# Sheet1.net
KiCad netlist of a schematic drawn in Altium Designer
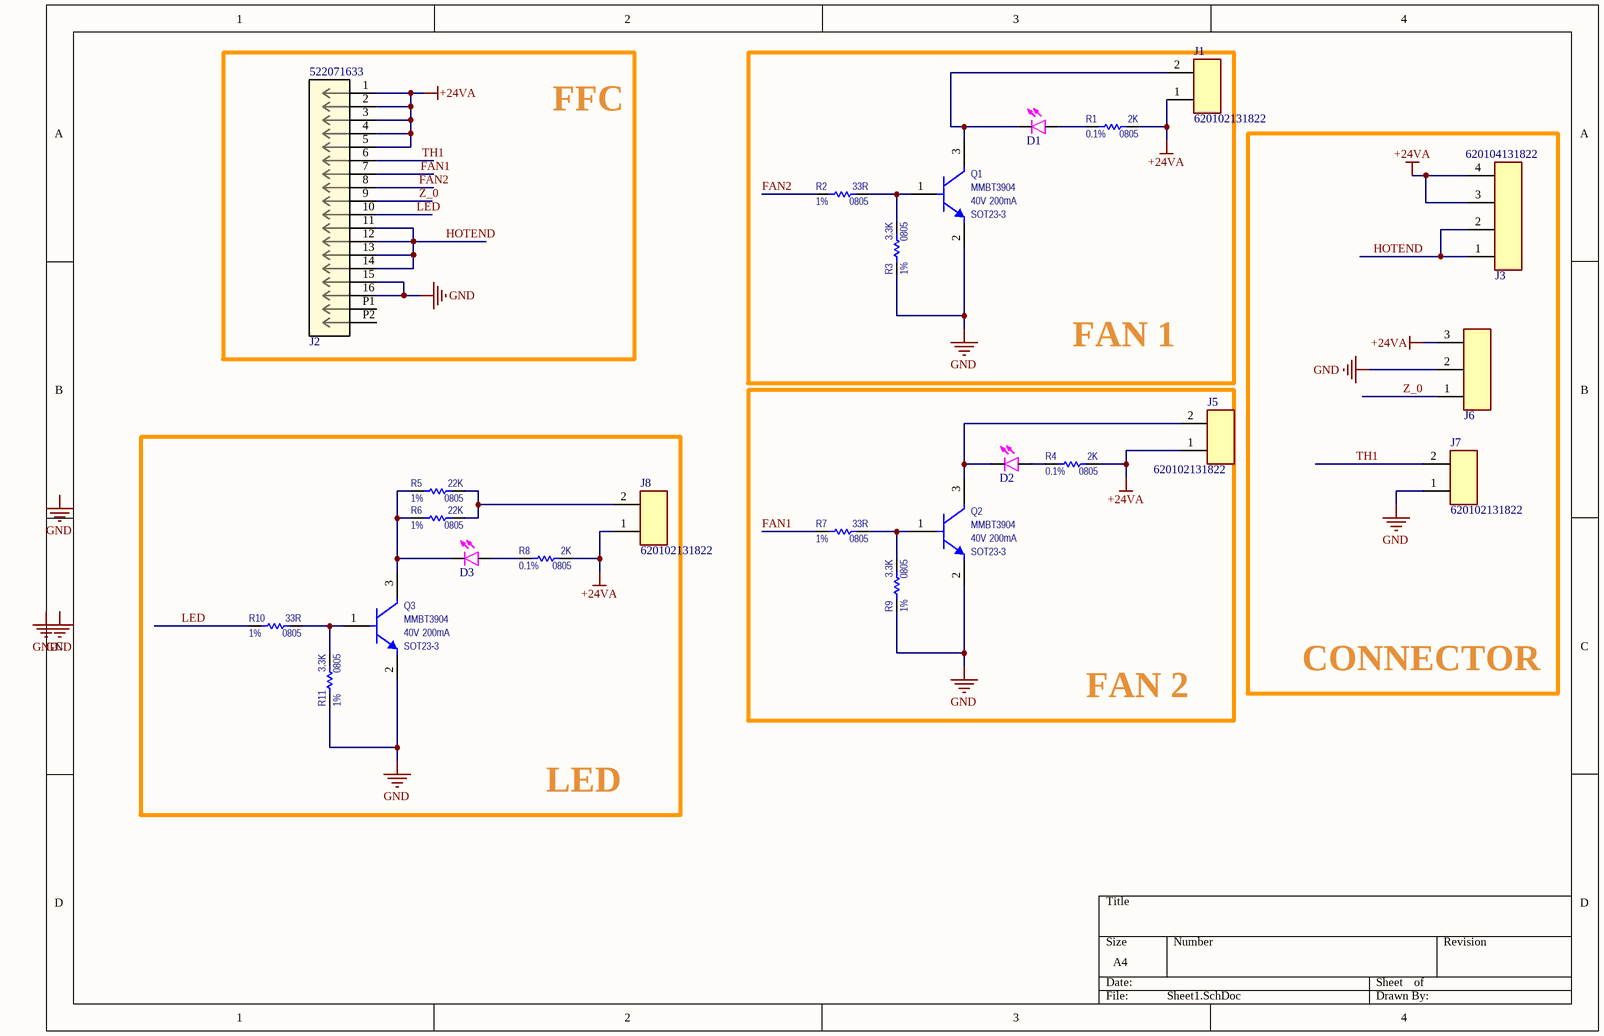
[diagram p0: Sheet1.SchDoc]

(export (version "E")
  (design (tool "Eeschema 10.0.6"))
  (components
    (comp (ref "D1")
      (value "KP-2012SRC-PRV")
      (footprint "0805 LED")
      (description "KP-2012SRC-PRV Red LED, 640 nm 2012 (0805), Rectangle Lens SMD package")
      (fields (field (name "MANUFACTURER") "Kingbright"))
      (libsource (lib "Schlib1") (part "KP-2012SRC-PRV"))
    )
    (comp (ref "D2")
      (value "KP-2012SRC-PRV")
      (footprint "0805 LED")
      (description "KP-2012SRC-PRV Red LED, 640 nm 2012 (0805), Rectangle Lens SMD package")
      (fields (field (name "MANUFACTURER") "Kingbright"))
      (libsource (lib "Schlib1") (part "KP-2012SRC-PRV"))
    )
    (comp (ref "D3")
      (value "KP-2012SRC-PRV")
      (footprint "0805 LED")
      (description "KP-2012SRC-PRV Red LED, 640 nm 2012 (0805), Rectangle Lens SMD package")
      (fields (field (name "MANUFACTURER") "Kingbright"))
      (libsource (lib "Schlib1") (part "KP-2012SRC-PRV"))
    )
    (comp (ref "J1")
      (value "620102131822")
      (footprint "620102131822")
      (description "Connector Header Surface Mount, Right Angle 2 position 0.079 _2.00mm_")
      (fields (field (name "MF") "Wurth Electronics"))
      (libsource (lib "Schlib1") (part "620102131822"))
    )
    (comp (ref "J2")
      (value "522071633")
      (footprint "CON_522071633_MOL")
      (description "No Description Available")
      (libsource (lib "Schlib1") (part "522071633"))
    )
    (comp (ref "J3")
      (value "620104131822")
      (footprint "620104131822")
      (libsource (lib "Schlib1") (part "620104131822"))
    )
    (comp (ref "J5")
      (value "620102131822")
      (footprint "620102131822")
      (description "Connector Header Surface Mount, Right Angle 2 position 0.079 _2.00mm_")
      (fields (field (name "MF") "Wurth Electronics"))
      (libsource (lib "Schlib1") (part "620102131822"))
    )
    (comp (ref "J6")
      (value "620103131822")
      (footprint "620103131822")
      (description "Connector Header Surface Mount, Right Angle 3 position 0.079 (2.00mm)")
      (fields (field (name "MF") "Wurth Electronics"))
      (libsource (lib "Schlib1") (part "620103131822"))
    )
    (comp (ref "J7")
      (value "620102131822")
      (footprint "620102131822")
      (description "Connector Header Surface Mount, Right Angle 2 position 0.079 _2.00mm_")
      (fields (field (name "MF") "Wurth Electronics"))
      (libsource (lib "Schlib1") (part "620102131822"))
    )
    (comp (ref "J8")
      (value "620102131822")
      (footprint "620102131822")
      (description "Connector Header Surface Mount, Right Angle 2 position 0.079 _2.00mm_")
      (fields (field (name "MF") "Wurth Electronics"))
      (libsource (lib "Schlib1") (part "620102131822"))
    )
    (comp (ref "Q1")
      (value "MMBT3904")
      (footprint "SOT23-3_MMBT3904,215")
      (description "TRA_NPN_SING_40V_200mA_VSAT300mV_SOT23-3")
      (fields
        (field (name "CURRENT") "200mA")
        (field (name "VOLTAGE") "40V")
        (field (name "PACKAGE") "SOT23-3")
        (field (name "SIMILAR PART") "SST3904HZGT116; PMBT3904,235")
        (field (name "TOLERANCE") "X")
        (field (name "ADDED BY") "HasanA")
        (field (name "CHECKED BY") "EserC")
      )
      (libsource (lib "FireANTs_HwLibDB") (part "SingleNPN_B1E2C3"))
    )
    (comp (ref "Q2")
      (value "MMBT3904")
      (footprint "SOT23-3_MMBT3904,215")
      (description "TRA_NPN_SING_40V_200mA_VSAT300mV_SOT23-3")
      (fields
        (field (name "CURRENT") "200mA")
        (field (name "VOLTAGE") "40V")
        (field (name "PACKAGE") "SOT23-3")
        (field (name "SIMILAR PART") "SST3904HZGT116; PMBT3904,235")
        (field (name "TOLERANCE") "X")
        (field (name "ADDED BY") "HasanA")
        (field (name "CHECKED BY") "EserC")
      )
      (libsource (lib "FireANTs_HwLibDB") (part "SingleNPN_B1E2C3"))
    )
    (comp (ref "Q3")
      (value "MMBT3904")
      (footprint "SOT23-3_MMBT3904,215")
      (description "TRA_NPN_SING_40V_200mA_VSAT300mV_SOT23-3")
      (fields
        (field (name "CURRENT") "200mA")
        (field (name "VOLTAGE") "40V")
        (field (name "PACKAGE") "SOT23-3")
        (field (name "SIMILAR PART") "SST3904HZGT116; PMBT3904,235")
        (field (name "TOLERANCE") "X")
        (field (name "ADDED BY") "HasanA")
        (field (name "CHECKED BY") "EserC")
      )
      (libsource (lib "FireANTs_HwLibDB") (part "SingleNPN_B1E2C3"))
    )
    (comp (ref "R1")
      (value "2K")
      (footprint "R_0805_GEN_0.70H")
      (description "RES_STD_2K_0.125W_0.1%_25ppm_0805")
      (fields
        (field (name "TOLERANCE") "0.1%")
        (field (name "PACKAGE") "0805")
        (field (name "SIMILAR PART") "ERA-6ARB202V")
        (field (name "VOLTAGE") "100V")
        (field (name "ADDED BY") "İlhanT")
        (field (name "CHECKED BY") "YasinY")
      )
      (libsource (lib "FireANTs_HwLibDB") (part "StandardResistor"))
    )
    (comp (ref "R2")
      (value "33R")
      (footprint "R_0805_GEN_0.70H")
      (description "RES_STD_33R_0.125W_1%_100ppm_0805")
      (fields
        (field (name "TOLERANCE") "1%")
        (field (name "PACKAGE") "0805")
        (field (name "VOLTAGE") "150V")
        (field (name "Comment") "StandardResistor")
        (field (name "ADDED BY") "HasanA")
        (field (name "CHECKED BY") "YasinY")
      )
      (libsource (lib "FireANTs_HwLibDB") (part "StandardResistor"))
    )
    (comp (ref "R3")
      (value "3.3K")
      (footprint "R_0805_GEN_0.70H")
      (description "RES_STD_3.3K_0.125W_1%_100ppm_0805")
      (fields
        (field (name "TOLERANCE") "1%")
        (field (name "PACKAGE") "0805")
        (field (name "VOLTAGE") "150V")
        (field (name "Comment") "StandardResistor")
        (field (name "ADDED BY") "HasanA")
        (field (name "CHECKED BY") "YasinY")
      )
      (libsource (lib "FireANTs_HwLibDB") (part "StandardResistor"))
    )
    (comp (ref "R4")
      (value "2K")
      (footprint "R_0805_GEN_0.70H")
      (description "RES_STD_2K_0.125W_0.1%_25ppm_0805")
      (fields
        (field (name "TOLERANCE") "0.1%")
        (field (name "PACKAGE") "0805")
        (field (name "SIMILAR PART") "ERA-6ARB202V")
        (field (name "VOLTAGE") "100V")
        (field (name "ADDED BY") "İlhanT")
        (field (name "CHECKED BY") "YasinY")
      )
      (libsource (lib "FireANTs_HwLibDB") (part "StandardResistor"))
    )
    (comp (ref "R5")
      (value "22K")
      (footprint "R_0805_GEN_0.70H")
      (description "RES_STD_33R_0.125W_1%_100ppm_0805")
      (fields
        (field (name "TOLERANCE") "1%")
        (field (name "PACKAGE") "0805")
        (field (name "VOLTAGE") "150V")
        (field (name "Comment") "StandardResistor")
        (field (name "ADDED BY") "HasanA")
        (field (name "CHECKED BY") "YasinY")
      )
      (libsource (lib "FireANTs_HwLibDB") (part "StandardResistor"))
    )
    (comp (ref "R6")
      (value "22K")
      (footprint "R_0805_GEN_0.70H")
      (description "RES_STD_33R_0.125W_1%_100ppm_0805")
      (fields
        (field (name "TOLERANCE") "1%")
        (field (name "PACKAGE") "0805")
        (field (name "VOLTAGE") "150V")
        (field (name "Comment") "StandardResistor")
        (field (name "ADDED BY") "HasanA")
        (field (name "CHECKED BY") "YasinY")
      )
      (libsource (lib "FireANTs_HwLibDB") (part "StandardResistor"))
    )
    (comp (ref "R7")
      (value "33R")
      (footprint "R_0805_GEN_0.70H")
      (description "RES_STD_33R_0.125W_1%_100ppm_0805")
      (fields
        (field (name "TOLERANCE") "1%")
        (field (name "PACKAGE") "0805")
        (field (name "VOLTAGE") "150V")
        (field (name "Comment") "StandardResistor")
        (field (name "ADDED BY") "HasanA")
        (field (name "CHECKED BY") "YasinY")
      )
      (libsource (lib "FireANTs_HwLibDB") (part "StandardResistor"))
    )
    (comp (ref "R8")
      (value "2K")
      (footprint "R_0805_GEN_0.70H")
      (description "RES_STD_2K_0.125W_0.1%_25ppm_0805")
      (fields
        (field (name "TOLERANCE") "0.1%")
        (field (name "PACKAGE") "0805")
        (field (name "SIMILAR PART") "ERA-6ARB202V")
        (field (name "VOLTAGE") "100V")
        (field (name "ADDED BY") "İlhanT")
        (field (name "CHECKED BY") "YasinY")
      )
      (libsource (lib "FireANTs_HwLibDB") (part "StandardResistor"))
    )
    (comp (ref "R9")
      (value "3.3K")
      (footprint "R_0805_GEN_0.70H")
      (description "RES_STD_3.3K_0.125W_1%_100ppm_0805")
      (fields
        (field (name "TOLERANCE") "1%")
        (field (name "PACKAGE") "0805")
        (field (name "VOLTAGE") "150V")
        (field (name "Comment") "StandardResistor")
        (field (name "ADDED BY") "HasanA")
        (field (name "CHECKED BY") "YasinY")
      )
      (libsource (lib "FireANTs_HwLibDB") (part "StandardResistor"))
    )
    (comp (ref "R10")
      (value "33R")
      (footprint "R_0805_GEN_0.70H")
      (description "RES_STD_33R_0.125W_1%_100ppm_0805")
      (fields
        (field (name "TOLERANCE") "1%")
        (field (name "PACKAGE") "0805")
        (field (name "VOLTAGE") "150V")
        (field (name "Comment") "StandardResistor")
        (field (name "ADDED BY") "HasanA")
        (field (name "CHECKED BY") "YasinY")
      )
      (libsource (lib "FireANTs_HwLibDB") (part "StandardResistor"))
    )
    (comp (ref "R11")
      (value "3.3K")
      (footprint "R_0805_GEN_0.70H")
      (description "RES_STD_3.3K_0.125W_1%_100ppm_0805")
      (fields
        (field (name "TOLERANCE") "1%")
        (field (name "PACKAGE") "0805")
        (field (name "VOLTAGE") "150V")
        (field (name "Comment") "StandardResistor")
        (field (name "ADDED BY") "HasanA")
        (field (name "CHECKED BY") "YasinY")
      )
      (libsource (lib "FireANTs_HwLibDB") (part "StandardResistor"))
    )
  )
  (nets
    (net (code "1") (name "+24VA") (class "Default")
      (node (ref "J1") (pin "1") (pinfunction "2_1") (pintype "passive"))
      (node (ref "J2") (pin "1") (pinfunction "1_1") (pintype "passive"))
      (node (ref "J2") (pin "2") (pinfunction "2_2") (pintype "passive"))
      (node (ref "J2") (pin "3") (pinfunction "3_3") (pintype "passive"))
      (node (ref "J2") (pin "4") (pinfunction "4_4") (pintype "passive"))
      (node (ref "J2") (pin "5") (pinfunction "5_5") (pintype "passive"))
      (node (ref "J3") (pin "3") (pinfunction "2_3") (pintype "passive"))
      (node (ref "J3") (pin "4") (pinfunction "1_4") (pintype "passive"))
      (node (ref "J5") (pin "1") (pinfunction "2_1") (pintype "passive"))
      (node (ref "J6") (pin "3") (pinfunction "1_3") (pintype "passive"))
      (node (ref "J8") (pin "1") (pinfunction "2_1") (pintype "passive"))
      (node (ref "R1") (pin "2") (pinfunction "2_2") (pintype "passive"))
      (node (ref "R4") (pin "2") (pinfunction "2_2") (pintype "passive"))
      (node (ref "R8") (pin "2") (pinfunction "2_2") (pintype "passive"))
    )
    (net (code "2") (name "/FAN1") (class "Default")
      (node (ref "J2") (pin "7") (pinfunction "7_7") (pintype "passive"))
      (node (ref "R7") (pin "1") (pinfunction "1_1") (pintype "passive"))
    )
    (net (code "3") (name "/FAN2") (class "Default")
      (node (ref "J2") (pin "8") (pinfunction "8_8") (pintype "passive"))
      (node (ref "R2") (pin "1") (pinfunction "1_1") (pintype "passive"))
    )
    (net (code "4") (name "/HOTEND") (class "Default")
      (node (ref "J2") (pin "11") (pinfunction "11_11") (pintype "passive"))
      (node (ref "J2") (pin "12") (pinfunction "12_12") (pintype "passive"))
      (node (ref "J2") (pin "13") (pinfunction "13_13") (pintype "passive"))
      (node (ref "J2") (pin "14") (pinfunction "14_14") (pintype "passive"))
      (node (ref "J3") (pin "1") (pinfunction "4_1") (pintype "passive"))
      (node (ref "J3") (pin "2") (pinfunction "3_2") (pintype "passive"))
    )
    (net (code "5") (name "/LED") (class "Default")
      (node (ref "J2") (pin "10") (pinfunction "10_10") (pintype "passive"))
      (node (ref "R10") (pin "1") (pinfunction "1_1") (pintype "passive"))
    )
    (net (code "6") (name "/TH1") (class "Default")
      (node (ref "J2") (pin "6") (pinfunction "6_6") (pintype "passive"))
      (node (ref "J7") (pin "2") (pinfunction "1_2") (pintype "passive"))
    )
    (net (code "7") (name "/Z_0") (class "Default")
      (node (ref "J2") (pin "9") (pinfunction "9_9") (pintype "passive"))
      (node (ref "J6") (pin "1") (pinfunction "3_1") (pintype "passive"))
    )
    (net (code "8") (name "GND") (class "Default")
      (node (ref "J2") (pin "15") (pinfunction "15_15") (pintype "passive"))
      (node (ref "J2") (pin "16") (pinfunction "16_16") (pintype "passive"))
      (node (ref "J6") (pin "2") (pinfunction "2_2") (pintype "passive"))
      (node (ref "J7") (pin "1") (pinfunction "2_1") (pintype "passive"))
      (node (ref "Q1") (pin "2") (pinfunction "EMITTER_2") (pintype "passive"))
      (node (ref "Q2") (pin "2") (pinfunction "EMITTER_2") (pintype "passive"))
      (node (ref "Q3") (pin "2") (pinfunction "EMITTER_2") (pintype "passive"))
      (node (ref "R11") (pin "1") (pinfunction "1_1") (pintype "passive"))
      (node (ref "R3") (pin "1") (pinfunction "1_1") (pintype "passive"))
      (node (ref "R9") (pin "1") (pinfunction "1_1") (pintype "passive"))
    )
    (net (code "9") (name "Net-(D1-C)") (class "Default")
      (node (ref "D1") (pin "K") (pinfunction "C_K") (pintype "passive"))
      (node (ref "J1") (pin "2") (pinfunction "1_2") (pintype "passive"))
      (node (ref "Q1") (pin "3") (pinfunction "COLLECTOR_3") (pintype "passive"))
    )
    (net (code "10") (name "Net-(D1-PadA)") (class "Default")
      (node (ref "D1") (pin "A") (pinfunction "A_A") (pintype "passive"))
      (node (ref "R1") (pin "1") (pinfunction "1_1") (pintype "passive"))
    )
    (net (code "11") (name "Net-(D2-C)") (class "Default")
      (node (ref "D2") (pin "K") (pinfunction "C_K") (pintype "passive"))
      (node (ref "J5") (pin "2") (pinfunction "1_2") (pintype "passive"))
      (node (ref "Q2") (pin "3") (pinfunction "COLLECTOR_3") (pintype "passive"))
    )
    (net (code "12") (name "Net-(D2-PadA)") (class "Default")
      (node (ref "D2") (pin "A") (pinfunction "A_A") (pintype "passive"))
      (node (ref "R4") (pin "1") (pinfunction "1_1") (pintype "passive"))
    )
    (net (code "13") (name "Net-(D3-C)") (class "Default")
      (node (ref "D3") (pin "K") (pinfunction "C_K") (pintype "passive"))
      (node (ref "Q3") (pin "3") (pinfunction "COLLECTOR_3") (pintype "passive"))
      (node (ref "R5") (pin "1") (pinfunction "1_1") (pintype "passive"))
      (node (ref "R6") (pin "1") (pinfunction "1_1") (pintype "passive"))
    )
    (net (code "14") (name "Net-(D3-PadA)") (class "Default")
      (node (ref "D3") (pin "A") (pinfunction "A_A") (pintype "passive"))
      (node (ref "R8") (pin "1") (pinfunction "1_1") (pintype "passive"))
    )
    (net (code "15") (name "Net-(J8-1)") (class "Default")
      (node (ref "J8") (pin "2") (pinfunction "1_2") (pintype "passive"))
      (node (ref "R5") (pin "2") (pinfunction "2_2") (pintype "passive"))
      (node (ref "R6") (pin "2") (pinfunction "2_2") (pintype "passive"))
    )
    (net (code "16") (name "Net-(Q1-BASE)") (class "Default")
      (node (ref "Q1") (pin "1") (pinfunction "BASE_1") (pintype "passive"))
      (node (ref "R2") (pin "2") (pinfunction "2_2") (pintype "passive"))
      (node (ref "R3") (pin "2") (pinfunction "2_2") (pintype "passive"))
    )
    (net (code "17") (name "Net-(Q2-BASE)") (class "Default")
      (node (ref "Q2") (pin "1") (pinfunction "BASE_1") (pintype "passive"))
      (node (ref "R7") (pin "2") (pinfunction "2_2") (pintype "passive"))
      (node (ref "R9") (pin "2") (pinfunction "2_2") (pintype "passive"))
    )
    (net (code "18") (name "Net-(Q3-BASE)") (class "Default")
      (node (ref "Q3") (pin "1") (pinfunction "BASE_1") (pintype "passive"))
      (node (ref "R10") (pin "2") (pinfunction "2_2") (pintype "passive"))
      (node (ref "R11") (pin "2") (pinfunction "2_2") (pintype "passive"))
    )
    (net (code "19") (name "unconnected-(J2-PadP1)") (class "Default")
      (node (ref "J2") (pin "P1") (pinfunction "P1_P1") (pintype "passive"))
    )
    (net (code "20") (name "unconnected-(J2-PadP2)") (class "Default")
      (node (ref "J2") (pin "P2") (pinfunction "P2_P2") (pintype "passive"))
    )
  )
)
